# AC_based_repeater_V3.net
KiCad netlist of a schematic drawn in EAGLE
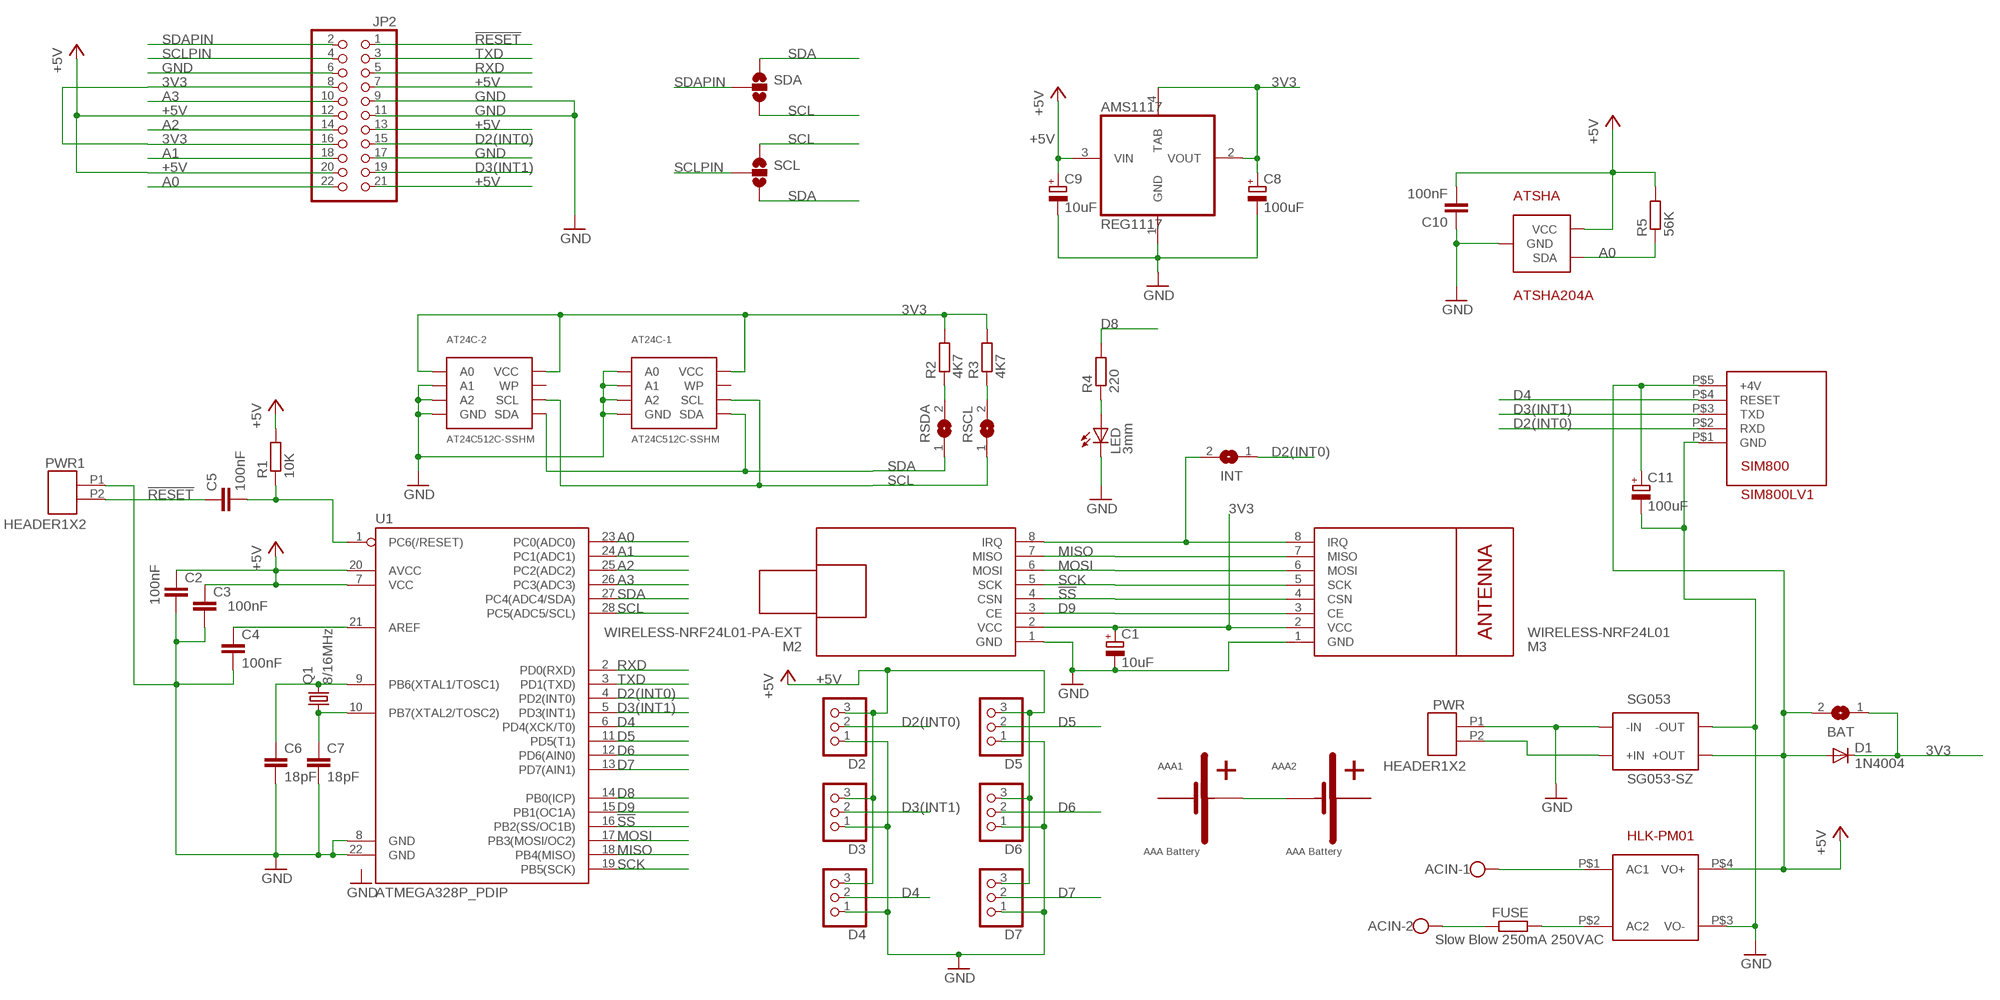
[diagram p0: schematic, sheet 1]

(export (version "E")
  (design (tool "Eeschema 10.0.6"))
  (components
    (comp (ref "AAA1")
      (value "AAA Battery")
      (footprint "eagle-import:AAABATTERYHOLDERPLUSPIN")
      (libsource (lib "eagle-import") (part "AAABATTERYPLUSPIN"))
    )
    (comp (ref "AAA2")
      (value "AAA Battery")
      (footprint "eagle-import:AAABATTERYHOLDERMINPIN")
      (libsource (lib "eagle-import") (part "AAABATTERYMINPIN"))
    )
    (comp (ref "ACIN")
      (value "W237-102")
      (footprint "eagle-import:W237-102")
      (fields (field (name "MPN") "237-102"))
      (libsource (lib "eagle-import") (part "W237-102"))
    )
    (comp (ref "AMS1117")
      (value "REG1117")
      (footprint "eagle-import:SOT223")
      (libsource (lib "eagle-import") (part "REG1117"))
    )
    (comp (ref "AT24C-1")
      (value "AT24C512C-SSHM")
      (footprint "eagle-import:SOIC8")
      (libsource (lib "eagle-import") (part "AT24C32SOIC8"))
    )
    (comp (ref "AT24C-2")
      (value "AT24C512C-SSHM")
      (footprint "eagle-import:SOIC8")
      (libsource (lib "eagle-import") (part "AT24C32SOIC8"))
    )
    (comp (ref "ATSHA")
      (value "ATSHA204A")
      (footprint "eagle-import:SOT23-R")
      (libsource (lib "eagle-import") (part "ATSHA204A"))
    )
    (comp (ref "BAT") (value "SJ") (footprint "eagle-import:SJ") (libsource (lib "eagle-import") (part "SJ")))
    (comp (ref "C1")
      (value "10uF")
      (footprint "eagle-import:E2,5-5")
      (libsource (lib "eagle-import") (part "CPOL-EUE2.5-5"))
    )
    (comp (ref "C2")
      (value "100nF")
      (footprint "eagle-import:C025-025X050")
      (libsource (lib "eagle-import") (part "C-EU025-025X050"))
    )
    (comp (ref "C3")
      (value "100nF")
      (footprint "eagle-import:C025-025X050")
      (libsource (lib "eagle-import") (part "C-EU025-025X050"))
    )
    (comp (ref "C4")
      (value "100nF")
      (footprint "eagle-import:C025-025X050")
      (libsource (lib "eagle-import") (part "C-EU025-025X050"))
    )
    (comp (ref "C5")
      (value "100nF")
      (footprint "eagle-import:C025-025X050")
      (libsource (lib "eagle-import") (part "C-EU025-025X050"))
    )
    (comp (ref "C6")
      (value "18pF")
      (footprint "eagle-import:C025-025X050")
      (libsource (lib "eagle-import") (part "C-EU025-025X050"))
    )
    (comp (ref "C7")
      (value "18pF")
      (footprint "eagle-import:C025-025X050")
      (libsource (lib "eagle-import") (part "C-EU025-025X050"))
    )
    (comp (ref "C8")
      (value "100uF")
      (footprint "eagle-import:E3,5-8")
      (libsource (lib "eagle-import") (part "CPOL-EUE3.5-8"))
    )
    (comp (ref "C9")
      (value "10uF")
      (footprint "eagle-import:E2,5-5")
      (libsource (lib "eagle-import") (part "CPOL-EUE2.5-5"))
    )
    (comp (ref "C10")
      (value "100nF")
      (footprint "eagle-import:C025-025X050")
      (libsource (lib "eagle-import") (part "C-EU025-025X050"))
    )
    (comp (ref "C11")
      (value "100uF")
      (footprint "eagle-import:E3,5-8")
      (libsource (lib "eagle-import") (part "CPOL-EUE3.5-8"))
    )
    (comp (ref "D1")
      (value "1N4004")
      (footprint "eagle-import:DO41-10")
      (libsource (lib "eagle-import") (part "1N4004"))
    )
    (comp (ref "D2")
      (value "PINHD-1X3PTH")
      (footprint "eagle-import:1X03")
      (libsource (lib "eagle-import") (part "PINHD-1X3PTH"))
    )
    (comp (ref "D3")
      (value "PINHD-1X3PTH")
      (footprint "eagle-import:1X03")
      (libsource (lib "eagle-import") (part "PINHD-1X3PTH"))
    )
    (comp (ref "D4")
      (value "PINHD-1X3PTH")
      (footprint "eagle-import:1X03")
      (libsource (lib "eagle-import") (part "PINHD-1X3PTH"))
    )
    (comp (ref "D5")
      (value "PINHD-1X3PTH")
      (footprint "eagle-import:1X03")
      (libsource (lib "eagle-import") (part "PINHD-1X3PTH"))
    )
    (comp (ref "D6")
      (value "PINHD-1X3PTH")
      (footprint "eagle-import:1X03")
      (libsource (lib "eagle-import") (part "PINHD-1X3PTH"))
    )
    (comp (ref "D7")
      (value "PINHD-1X3PTH")
      (footprint "eagle-import:1X03")
      (libsource (lib "eagle-import") (part "PINHD-1X3PTH"))
    )
    (comp (ref "FUSE")
      (value "Slow Blow 250mA 250VAC")
      (footprint "eagle-import:0411V")
      (libsource (lib "eagle-import") (part "R-EU_0411/3V"))
    )
    (comp (ref "HLK-PM01")
      (value "HLK-PM01")
      (footprint "eagle-import:HLK-PM01")
      (libsource (lib "eagle-import") (part "HLK-PM01"))
    )
    (comp (ref "INT") (value "SJ") (footprint "eagle-import:SJ") (libsource (lib "eagle-import") (part "SJ")))
    (comp (ref "JP2")
      (value "PINHD-2X11")
      (footprint "eagle-import:2X11")
      (libsource (lib "eagle-import") (part "PINHD-2X11"))
    )
    (comp (ref "LED")
      (value "3mm")
      (footprint "eagle-import:LED3MM")
      (libsource (lib "eagle-import") (part "LED3MM"))
    )
    (comp (ref "M2")
      (value "WIRELESS-NRF24L01-PA-EXT")
      (footprint "eagle-import:WIRELESS-NRD24L01-PA-EXT")
      (libsource (lib "eagle-import") (part "WIRELESS-NRF24L01-PA-EXT"))
    )
    (comp (ref "M3")
      (value "WIRELESS-NRF24L01")
      (footprint "eagle-import:WIRELESS-NRF24L01")
      (libsource (lib "eagle-import") (part "WIRELESS-NRF24L01"))
    )
    (comp (ref "PWR")
      (value "HEADER1X2")
      (footprint "eagle-import:HEADER1X2")
      (libsource (lib "eagle-import") (part "HEADER1X2"))
    )
    (comp (ref "PWR1")
      (value "HEADER1X2")
      (footprint "eagle-import:HEADER1X2")
      (libsource (lib "eagle-import") (part "HEADER1X2"))
    )
    (comp (ref "Q1")
      (value "8/16MHz")
      (footprint "eagle-import:HC49U-V")
      (libsource (lib "eagle-import") (part "CRYSTALHC49U-V"))
    )
    (comp (ref "R1")
      (value "10K")
      (footprint "eagle-import:0207_7")
      (libsource (lib "eagle-import") (part "R-EU_0207/7"))
    )
    (comp (ref "R2")
      (value "4K7")
      (footprint "eagle-import:0207_7")
      (libsource (lib "eagle-import") (part "R-EU_0207/7"))
    )
    (comp (ref "R3")
      (value "4K7")
      (footprint "eagle-import:0207_7")
      (libsource (lib "eagle-import") (part "R-EU_0207/7"))
    )
    (comp (ref "R4")
      (value "220")
      (footprint "eagle-import:0207_7")
      (libsource (lib "eagle-import") (part "R-EU_0207/7"))
    )
    (comp (ref "R5")
      (value "56K")
      (footprint "eagle-import:0207_7")
      (libsource (lib "eagle-import") (part "R-EU_0207/7"))
    )
    (comp (ref "RSCL")
      (value "SJ")
      (footprint "eagle-import:SJ")
      (libsource (lib "eagle-import") (part "SJ"))
    )
    (comp (ref "RSDA")
      (value "SJ")
      (footprint "eagle-import:SJ")
      (libsource (lib "eagle-import") (part "SJ"))
    )
    (comp (ref "SCL")
      (value "JUMPER-PAD-3-NC_BY_TRACE")
      (footprint "eagle-import:PAD-JUMPER-3-3OF3_NC_BY_TRACE_YES_SILK_FULL_BOX")
      (libsource (lib "eagle-import") (part "JUMPER-PAD-3-NC_BY_TRACE"))
    )
    (comp (ref "SDA")
      (value "JUMPER-PAD-3-NC_BY_TRACE")
      (footprint "eagle-import:PAD-JUMPER-3-3OF3_NC_BY_TRACE_YES_SILK_FULL_BOX")
      (libsource (lib "eagle-import") (part "JUMPER-PAD-3-NC_BY_TRACE"))
    )
    (comp (ref "SG053")
      (value "SG053-SZ")
      (footprint "eagle-import:SG053-SZ")
      (libsource (lib "eagle-import") (part "SG053-SZ"))
    )
    (comp (ref "SIM800")
      (value "SIM800LV1")
      (footprint "eagle-import:SIM800LV1")
      (libsource (lib "eagle-import") (part "SIM800LV1"))
    )
    (comp (ref "U1")
      (value "ATMEGA328P_PDIP")
      (footprint "eagle-import:DIL28-3")
      (libsource (lib "eagle-import") (part "ATMEGA328P_PDIP"))
    )
  )
  (nets
    (net (code "1") (name "+5V") (class "Default")
      (node (ref "AMS1117") (pin "3") (pinfunction "VIN_3") (pintype "input"))
      (node (ref "ATSHA") (pin "2") (pinfunction "VCC_2") (pintype "bidirectional"))
      (node (ref "BAT") (pin "2") (pinfunction "2_2") (pintype "passive"))
      (node (ref "C10") (pin "2") (pinfunction "2_2") (pintype "passive"))
      (node (ref "C11") (pin "+") (pinfunction "+_+") (pintype "passive"))
      (node (ref "C2") (pin "1") (pinfunction "1_1") (pintype "passive"))
      (node (ref "C3") (pin "1") (pinfunction "1_1") (pintype "passive"))
      (node (ref "C9") (pin "+") (pinfunction "+_+") (pintype "passive"))
      (node (ref "D1") (pin "A") (pinfunction "A_A") (pintype "passive"))
      (node (ref "D2") (pin "3") (pinfunction "3_3") (pintype "passive"))
      (node (ref "D3") (pin "3") (pinfunction "3_3") (pintype "passive"))
      (node (ref "D4") (pin "3") (pinfunction "3_3") (pintype "passive"))
      (node (ref "D5") (pin "3") (pinfunction "3_3") (pintype "passive"))
      (node (ref "D6") (pin "3") (pinfunction "3_3") (pintype "passive"))
      (node (ref "D7") (pin "3") (pinfunction "3_3") (pintype "passive"))
      (node (ref "HLK-PM01") (pin "P$4") (pinfunction "VO+_P$4") (pintype "power_in"))
      (node (ref "JP2") (pin "12") (pinfunction "12_12") (pintype "passive"))
      (node (ref "JP2") (pin "13") (pinfunction "13_13") (pintype "passive"))
      (node (ref "JP2") (pin "20") (pinfunction "20_20") (pintype "passive"))
      (node (ref "JP2") (pin "21") (pinfunction "21_21") (pintype "passive"))
      (node (ref "JP2") (pin "7") (pinfunction "7_7") (pintype "passive"))
      (node (ref "R1") (pin "2") (pinfunction "2_2") (pintype "passive"))
      (node (ref "R5") (pin "2") (pinfunction "2_2") (pintype "passive"))
      (node (ref "SG053") (pin "P$5") (pinfunction "+OUT_P$5") (pintype "bidirectional"))
      (node (ref "SG053") (pin "P$6") (pinfunction "+OUT_P$6") (pintype "bidirectional"))
      (node (ref "SIM800") (pin "P$5") (pinfunction "+4V_P$5") (pintype "power_in"))
      (node (ref "U1") (pin "20") (pinfunction "AVCC_20") (pintype "bidirectional"))
      (node (ref "U1") (pin "7") (pinfunction "VCC_7") (pintype "bidirectional"))
    )
    (net (code "2") (name "/3V3") (class "Default")
      (node (ref "AMS1117") (pin "2") (pinfunction "VOUT_2") (pintype "output"))
      (node (ref "AMS1117") (pin "4") (pinfunction "TAB_4") (pintype "bidirectional"))
      (node (ref "AT24C-1") (pin "8") (pinfunction "VCC_8") (pintype "power_in"))
      (node (ref "AT24C-2") (pin "1") (pinfunction "A0_1") (pintype "bidirectional"))
      (node (ref "AT24C-2") (pin "8") (pinfunction "VCC_8") (pintype "power_in"))
      (node (ref "BAT") (pin "1") (pinfunction "1_1") (pintype "passive"))
      (node (ref "C1") (pin "+") (pinfunction "+_+") (pintype "passive"))
      (node (ref "C8") (pin "+") (pinfunction "+_+") (pintype "passive"))
      (node (ref "D1") (pin "C") (pinfunction "C_C") (pintype "passive"))
      (node (ref "JP2") (pin "16") (pinfunction "16_16") (pintype "passive"))
      (node (ref "JP2") (pin "8") (pinfunction "8_8") (pintype "passive"))
      (node (ref "M2") (pin "2") (pinfunction "VCC_2") (pintype "power_in"))
      (node (ref "M3") (pin "2") (pinfunction "VCC_2") (pintype "power_in"))
      (node (ref "R2") (pin "2") (pinfunction "2_2") (pintype "passive"))
      (node (ref "R3") (pin "2") (pinfunction "2_2") (pintype "passive"))
    )
    (net (code "3") (name "/A0") (class "Default")
      (node (ref "ATSHA") (pin "1") (pinfunction "SDA_1") (pintype "bidirectional"))
      (node (ref "JP2") (pin "22") (pinfunction "22_22") (pintype "passive"))
      (node (ref "R5") (pin "1") (pinfunction "1_1") (pintype "passive"))
      (node (ref "U1") (pin "23") (pinfunction "PC0(ADC0)_23") (pintype "bidirectional"))
    )
    (net (code "4") (name "/A1") (class "Default")
      (node (ref "JP2") (pin "18") (pinfunction "18_18") (pintype "passive"))
      (node (ref "U1") (pin "24") (pinfunction "PC1(ADC1)_24") (pintype "bidirectional"))
    )
    (net (code "5") (name "/A2") (class "Default")
      (node (ref "JP2") (pin "14") (pinfunction "14_14") (pintype "passive"))
      (node (ref "U1") (pin "25") (pinfunction "PC2(ADC2)_25") (pintype "bidirectional"))
    )
    (net (code "6") (name "/A3") (class "Default")
      (node (ref "JP2") (pin "10") (pinfunction "10_10") (pintype "passive"))
      (node (ref "U1") (pin "26") (pinfunction "PC3(ADC3)_26") (pintype "bidirectional"))
    )
    (net (code "7") (name "/D2(INT0)") (class "Default")
      (node (ref "D2") (pin "2") (pinfunction "2_2") (pintype "passive"))
      (node (ref "INT") (pin "1") (pinfunction "1_1") (pintype "passive"))
      (node (ref "JP2") (pin "15") (pinfunction "15_15") (pintype "passive"))
      (node (ref "SIM800") (pin "P$2") (pinfunction "RXD_P$2") (pintype "input"))
      (node (ref "U1") (pin "4") (pinfunction "PD2(INT0)_4") (pintype "bidirectional"))
    )
    (net (code "8") (name "/D3(INT1)") (class "Default")
      (node (ref "D3") (pin "2") (pinfunction "2_2") (pintype "passive"))
      (node (ref "JP2") (pin "19") (pinfunction "19_19") (pintype "passive"))
      (node (ref "SIM800") (pin "P$3") (pinfunction "TXD_P$3") (pintype "output"))
      (node (ref "U1") (pin "5") (pinfunction "PD3(INT1)_5") (pintype "bidirectional"))
    )
    (net (code "9") (name "/D4") (class "Default")
      (node (ref "D4") (pin "2") (pinfunction "2_2") (pintype "passive"))
      (node (ref "SIM800") (pin "P$4") (pinfunction "RESET_P$4") (pintype "input"))
      (node (ref "U1") (pin "6") (pinfunction "PD4(XCK/T0)_6") (pintype "bidirectional"))
    )
    (net (code "10") (name "/D5") (class "Default")
      (node (ref "D5") (pin "2") (pinfunction "2_2") (pintype "passive"))
      (node (ref "U1") (pin "11") (pinfunction "PD5(T1)_11") (pintype "bidirectional"))
    )
    (net (code "11") (name "/D6") (class "Default")
      (node (ref "D6") (pin "2") (pinfunction "2_2") (pintype "passive"))
      (node (ref "U1") (pin "12") (pinfunction "PD6(AIN0)_12") (pintype "bidirectional"))
    )
    (net (code "12") (name "/D7") (class "Default")
      (node (ref "D7") (pin "2") (pinfunction "2_2") (pintype "passive"))
      (node (ref "U1") (pin "13") (pinfunction "PD7(AIN1)_13") (pintype "bidirectional"))
    )
    (net (code "13") (name "/D8") (class "Default")
      (node (ref "R4") (pin "2") (pinfunction "2_2") (pintype "passive"))
      (node (ref "U1") (pin "14") (pinfunction "PB0(ICP)_14") (pintype "bidirectional"))
    )
    (net (code "14") (name "/D9") (class "Default")
      (node (ref "M2") (pin "3") (pinfunction "CE_3") (pintype "bidirectional"))
      (node (ref "M3") (pin "3") (pinfunction "CE_3") (pintype "bidirectional"))
      (node (ref "U1") (pin "15") (pinfunction "PB1(OC1A)_15") (pintype "bidirectional"))
    )
    (net (code "15") (name "/MISO") (class "Default")
      (node (ref "M2") (pin "7") (pinfunction "MISO_7") (pintype "bidirectional"))
      (node (ref "M3") (pin "7") (pinfunction "MISO_7") (pintype "bidirectional"))
      (node (ref "U1") (pin "18") (pinfunction "PB4(MISO)_18") (pintype "bidirectional"))
    )
    (net (code "16") (name "/MOSI") (class "Default")
      (node (ref "M2") (pin "6") (pinfunction "MOSI_6") (pintype "bidirectional"))
      (node (ref "M3") (pin "6") (pinfunction "MOSI_6") (pintype "bidirectional"))
      (node (ref "U1") (pin "17") (pinfunction "PB3(MOSI/OC2)_17") (pintype "bidirectional"))
    )
    (net (code "17") (name "/RXD") (class "Default")
      (node (ref "JP2") (pin "5") (pinfunction "5_5") (pintype "passive"))
      (node (ref "U1") (pin "2") (pinfunction "PD0(RXD)_2") (pintype "bidirectional"))
    )
    (net (code "18") (name "/SCK") (class "Default")
      (node (ref "M2") (pin "5") (pinfunction "SCK_5") (pintype "bidirectional"))
      (node (ref "M3") (pin "5") (pinfunction "SCK_5") (pintype "bidirectional"))
      (node (ref "U1") (pin "19") (pinfunction "PB5(SCK)_19") (pintype "bidirectional"))
    )
    (net (code "19") (name "/SCL") (class "Default")
      (node (ref "AT24C-1") (pin "6") (pinfunction "SCL_6") (pintype "bidirectional"))
      (node (ref "AT24C-2") (pin "6") (pinfunction "SCL_6") (pintype "bidirectional"))
      (node (ref "RSCL") (pin "1") (pinfunction "1_1") (pintype "passive"))
      (node (ref "SCL") (pin "1") (pinfunction "1_1") (pintype "passive"))
      (node (ref "SDA") (pin "3") (pinfunction "3_3") (pintype "passive"))
      (node (ref "U1") (pin "28") (pinfunction "PC5(ADC5/SCL)_28") (pintype "bidirectional"))
    )
    (net (code "20") (name "/SCLPIN") (class "Default")
      (node (ref "JP2") (pin "4") (pinfunction "4_4") (pintype "passive"))
      (node (ref "SCL") (pin "2") (pinfunction "2_2") (pintype "passive"))
    )
    (net (code "21") (name "/SDA") (class "Default")
      (node (ref "AT24C-1") (pin "5") (pinfunction "SDA_5") (pintype "bidirectional"))
      (node (ref "AT24C-2") (pin "5") (pinfunction "SDA_5") (pintype "bidirectional"))
      (node (ref "RSDA") (pin "1") (pinfunction "1_1") (pintype "passive"))
      (node (ref "SCL") (pin "3") (pinfunction "3_3") (pintype "passive"))
      (node (ref "SDA") (pin "1") (pinfunction "1_1") (pintype "passive"))
      (node (ref "U1") (pin "27") (pinfunction "PC4(ADC4/SDA)_27") (pintype "bidirectional"))
    )
    (net (code "22") (name "/SDAPIN") (class "Default")
      (node (ref "JP2") (pin "2") (pinfunction "2_2") (pintype "passive"))
      (node (ref "SDA") (pin "2") (pinfunction "2_2") (pintype "passive"))
    )
    (net (code "23") (name "/TXD") (class "Default")
      (node (ref "JP2") (pin "3") (pinfunction "3_3") (pintype "passive"))
      (node (ref "U1") (pin "3") (pinfunction "PD1(TXD)_3") (pintype "bidirectional"))
    )
    (net (code "24") (name "/~{RESET}") (class "Default")
      (node (ref "C5") (pin "1") (pinfunction "1_1") (pintype "passive"))
      (node (ref "JP2") (pin "1") (pinfunction "1_1") (pintype "passive"))
      (node (ref "PWR1") (pin "P2") (pinfunction "P$2_P2") (pintype "bidirectional"))
    )
    (net (code "25") (name "/~{SS}") (class "Default")
      (node (ref "M2") (pin "4") (pinfunction "CSN_4") (pintype "bidirectional"))
      (node (ref "M3") (pin "4") (pinfunction "CSN_4") (pintype "bidirectional"))
      (node (ref "U1") (pin "16") (pinfunction "PB2(SS/OC1B)_16") (pintype "bidirectional"))
    )
    (net (code "26") (name "GND") (class "Default")
      (node (ref "AMS1117") (pin "1") (pinfunction "GND_1") (pintype "power_in"))
      (node (ref "AT24C-1") (pin "1") (pinfunction "A0_1") (pintype "bidirectional"))
      (node (ref "AT24C-1") (pin "2") (pinfunction "A1_2") (pintype "bidirectional"))
      (node (ref "AT24C-1") (pin "3") (pinfunction "A2_3") (pintype "bidirectional"))
      (node (ref "AT24C-1") (pin "4") (pinfunction "GND_4") (pintype "power_in"))
      (node (ref "AT24C-2") (pin "2") (pinfunction "A1_2") (pintype "bidirectional"))
      (node (ref "AT24C-2") (pin "3") (pinfunction "A2_3") (pintype "bidirectional"))
      (node (ref "AT24C-2") (pin "4") (pinfunction "GND_4") (pintype "power_in"))
      (node (ref "ATSHA") (pin "3") (pinfunction "GND_3") (pintype "bidirectional"))
      (node (ref "C1") (pin "-") (pinfunction "-_-") (pintype "passive"))
      (node (ref "C10") (pin "1") (pinfunction "1_1") (pintype "passive"))
      (node (ref "C11") (pin "-") (pinfunction "-_-") (pintype "passive"))
      (node (ref "C2") (pin "2") (pinfunction "2_2") (pintype "passive"))
      (node (ref "C3") (pin "2") (pinfunction "2_2") (pintype "passive"))
      (node (ref "C4") (pin "2") (pinfunction "2_2") (pintype "passive"))
      (node (ref "C6") (pin "2") (pinfunction "2_2") (pintype "passive"))
      (node (ref "C7") (pin "2") (pinfunction "2_2") (pintype "passive"))
      (node (ref "C8") (pin "-") (pinfunction "-_-") (pintype "passive"))
      (node (ref "C9") (pin "-") (pinfunction "-_-") (pintype "passive"))
      (node (ref "D2") (pin "1") (pinfunction "1_1") (pintype "passive"))
      (node (ref "D3") (pin "1") (pinfunction "1_1") (pintype "passive"))
      (node (ref "D4") (pin "1") (pinfunction "1_1") (pintype "passive"))
      (node (ref "D5") (pin "1") (pinfunction "1_1") (pintype "passive"))
      (node (ref "D6") (pin "1") (pinfunction "1_1") (pintype "passive"))
      (node (ref "D7") (pin "1") (pinfunction "1_1") (pintype "passive"))
      (node (ref "HLK-PM01") (pin "P$3") (pinfunction "VO-_P$3") (pintype "power_in"))
      (node (ref "JP2") (pin "11") (pinfunction "11_11") (pintype "passive"))
      (node (ref "JP2") (pin "17") (pinfunction "17_17") (pintype "passive"))
      (node (ref "JP2") (pin "6") (pinfunction "6_6") (pintype "passive"))
      (node (ref "JP2") (pin "9") (pinfunction "9_9") (pintype "passive"))
      (node (ref "LED") (pin "K") (pinfunction "C_K") (pintype "passive"))
      (node (ref "M2") (pin "1") (pinfunction "GND_1") (pintype "power_in"))
      (node (ref "M3") (pin "1") (pinfunction "GND_1") (pintype "power_in"))
      (node (ref "PWR") (pin "P1") (pinfunction "P$1_P1") (pintype "bidirectional"))
      (node (ref "PWR1") (pin "P1") (pinfunction "P$1_P1") (pintype "bidirectional"))
      (node (ref "SG053") (pin "P$1") (pinfunction "-IN_P$1") (pintype "bidirectional"))
      (node (ref "SG053") (pin "P$2") (pinfunction "-IN_P$2") (pintype "bidirectional"))
      (node (ref "SG053") (pin "P$7") (pinfunction "-OUT_P$7") (pintype "bidirectional"))
      (node (ref "SG053") (pin "P$8") (pinfunction "-OUT_P$8") (pintype "bidirectional"))
      (node (ref "SIM800") (pin "P$1") (pinfunction "GND_P$1") (pintype "power_in"))
      (node (ref "U1") (pin "22") (pinfunction "GND_22") (pintype "bidirectional"))
      (node (ref "U1") (pin "8") (pinfunction "GND_8") (pintype "bidirectional"))
    )
    (net (code "27") (name "Net-(AAA1-PadP$2)") (class "Default")
      (node (ref "AAA1") (pin "P$2") (pinfunction "P$2_P$2") (pintype "bidirectional"))
      (node (ref "AAA2") (pin "P$1") (pinfunction "P$1_P$1") (pintype "bidirectional"))
    )
    (net (code "28") (name "Net-(ACINA-KL)") (class "Default")
      (node (ref "ACIN") (pin "1") (pinfunction "KL_1") (pintype "passive"))
      (node (ref "HLK-PM01") (pin "P$1") (pinfunction "AC1_P$1") (pintype "input"))
    )
    (net (code "29") (name "Net-(ACINB-KL)") (class "Default")
      (node (ref "ACIN") (pin "2") (pinfunction "KL_2") (pintype "passive"))
      (node (ref "FUSE") (pin "1") (pinfunction "1_1") (pintype "passive"))
    )
    (net (code "30") (name "Net-(HLK-PM01-AC2)") (class "Default")
      (node (ref "FUSE") (pin "2") (pinfunction "2_2") (pintype "passive"))
      (node (ref "HLK-PM01") (pin "P$2") (pinfunction "AC2_P$2") (pintype "input"))
    )
    (net (code "31") (name "Net-(LED-PadA)") (class "Default")
      (node (ref "LED") (pin "A") (pinfunction "A_A") (pintype "passive"))
      (node (ref "R4") (pin "1") (pinfunction "1_1") (pintype "passive"))
    )
    (net (code "32") (name "Net-(M2-IRQ)") (class "Default")
      (node (ref "INT") (pin "2") (pinfunction "2_2") (pintype "passive"))
      (node (ref "M2") (pin "8") (pinfunction "IRQ_8") (pintype "bidirectional"))
      (node (ref "M3") (pin "8") (pinfunction "IRQ_8") (pintype "bidirectional"))
    )
    (net (code "33") (name "Net-(PWR-P$2)") (class "Default")
      (node (ref "PWR") (pin "P2") (pinfunction "P$2_P2") (pintype "bidirectional"))
      (node (ref "SG053") (pin "P$3") (pinfunction "+IN_P$3") (pintype "bidirectional"))
      (node (ref "SG053") (pin "P$4") (pinfunction "+IN_P$4") (pintype "bidirectional"))
    )
    (net (code "34") (name "Net-(R2-Pad1)") (class "Default")
      (node (ref "R2") (pin "1") (pinfunction "1_1") (pintype "passive"))
      (node (ref "RSDA") (pin "2") (pinfunction "2_2") (pintype "passive"))
    )
    (net (code "35") (name "Net-(R3-Pad1)") (class "Default")
      (node (ref "R3") (pin "1") (pinfunction "1_1") (pintype "passive"))
      (node (ref "RSCL") (pin "2") (pinfunction "2_2") (pintype "passive"))
    )
    (net (code "36") (name "Net-(U1-AREF)") (class "Default")
      (node (ref "C4") (pin "1") (pinfunction "1_1") (pintype "passive"))
      (node (ref "U1") (pin "21") (pinfunction "AREF_21") (pintype "bidirectional"))
    )
    (net (code "37") (name "Net-(U1-PB6(XTAL1{slash}TOSC1))") (class "Default")
      (node (ref "C6") (pin "1") (pinfunction "1_1") (pintype "passive"))
      (node (ref "Q1") (pin "2") (pinfunction "2_2") (pintype "passive"))
      (node (ref "U1") (pin "9") (pinfunction "PB6(XTAL1/TOSC1)_9") (pintype "bidirectional"))
    )
    (net (code "38") (name "Net-(U1-PB7(XTAL2{slash}TOSC2))") (class "Default")
      (node (ref "C7") (pin "1") (pinfunction "1_1") (pintype "passive"))
      (node (ref "Q1") (pin "1") (pinfunction "1_1") (pintype "passive"))
      (node (ref "U1") (pin "10") (pinfunction "PB7(XTAL2/TOSC2)_10") (pintype "bidirectional"))
    )
    (net (code "39") (name "Net-(U1-PC6({slash}RESET))") (class "Default")
      (node (ref "C5") (pin "2") (pinfunction "2_2") (pintype "passive"))
      (node (ref "R1") (pin "1") (pinfunction "1_1") (pintype "passive"))
      (node (ref "U1") (pin "1") (pinfunction "PC6(/RESET)_1") (pintype "bidirectional"))
    )
    (net (code "40") (name "unconnected-(AT24C-1-WP-Pad7)") (class "Default")
      (node (ref "AT24C-1") (pin "7") (pinfunction "WP_7") (pintype "bidirectional"))
    )
    (net (code "41") (name "unconnected-(AT24C-2-WP-Pad7)") (class "Default")
      (node (ref "AT24C-2") (pin "7") (pinfunction "WP_7") (pintype "bidirectional"))
    )
  )
)
